# preamp_transistor.net
KiCad netlist of a schematic drawn in EasyEDA
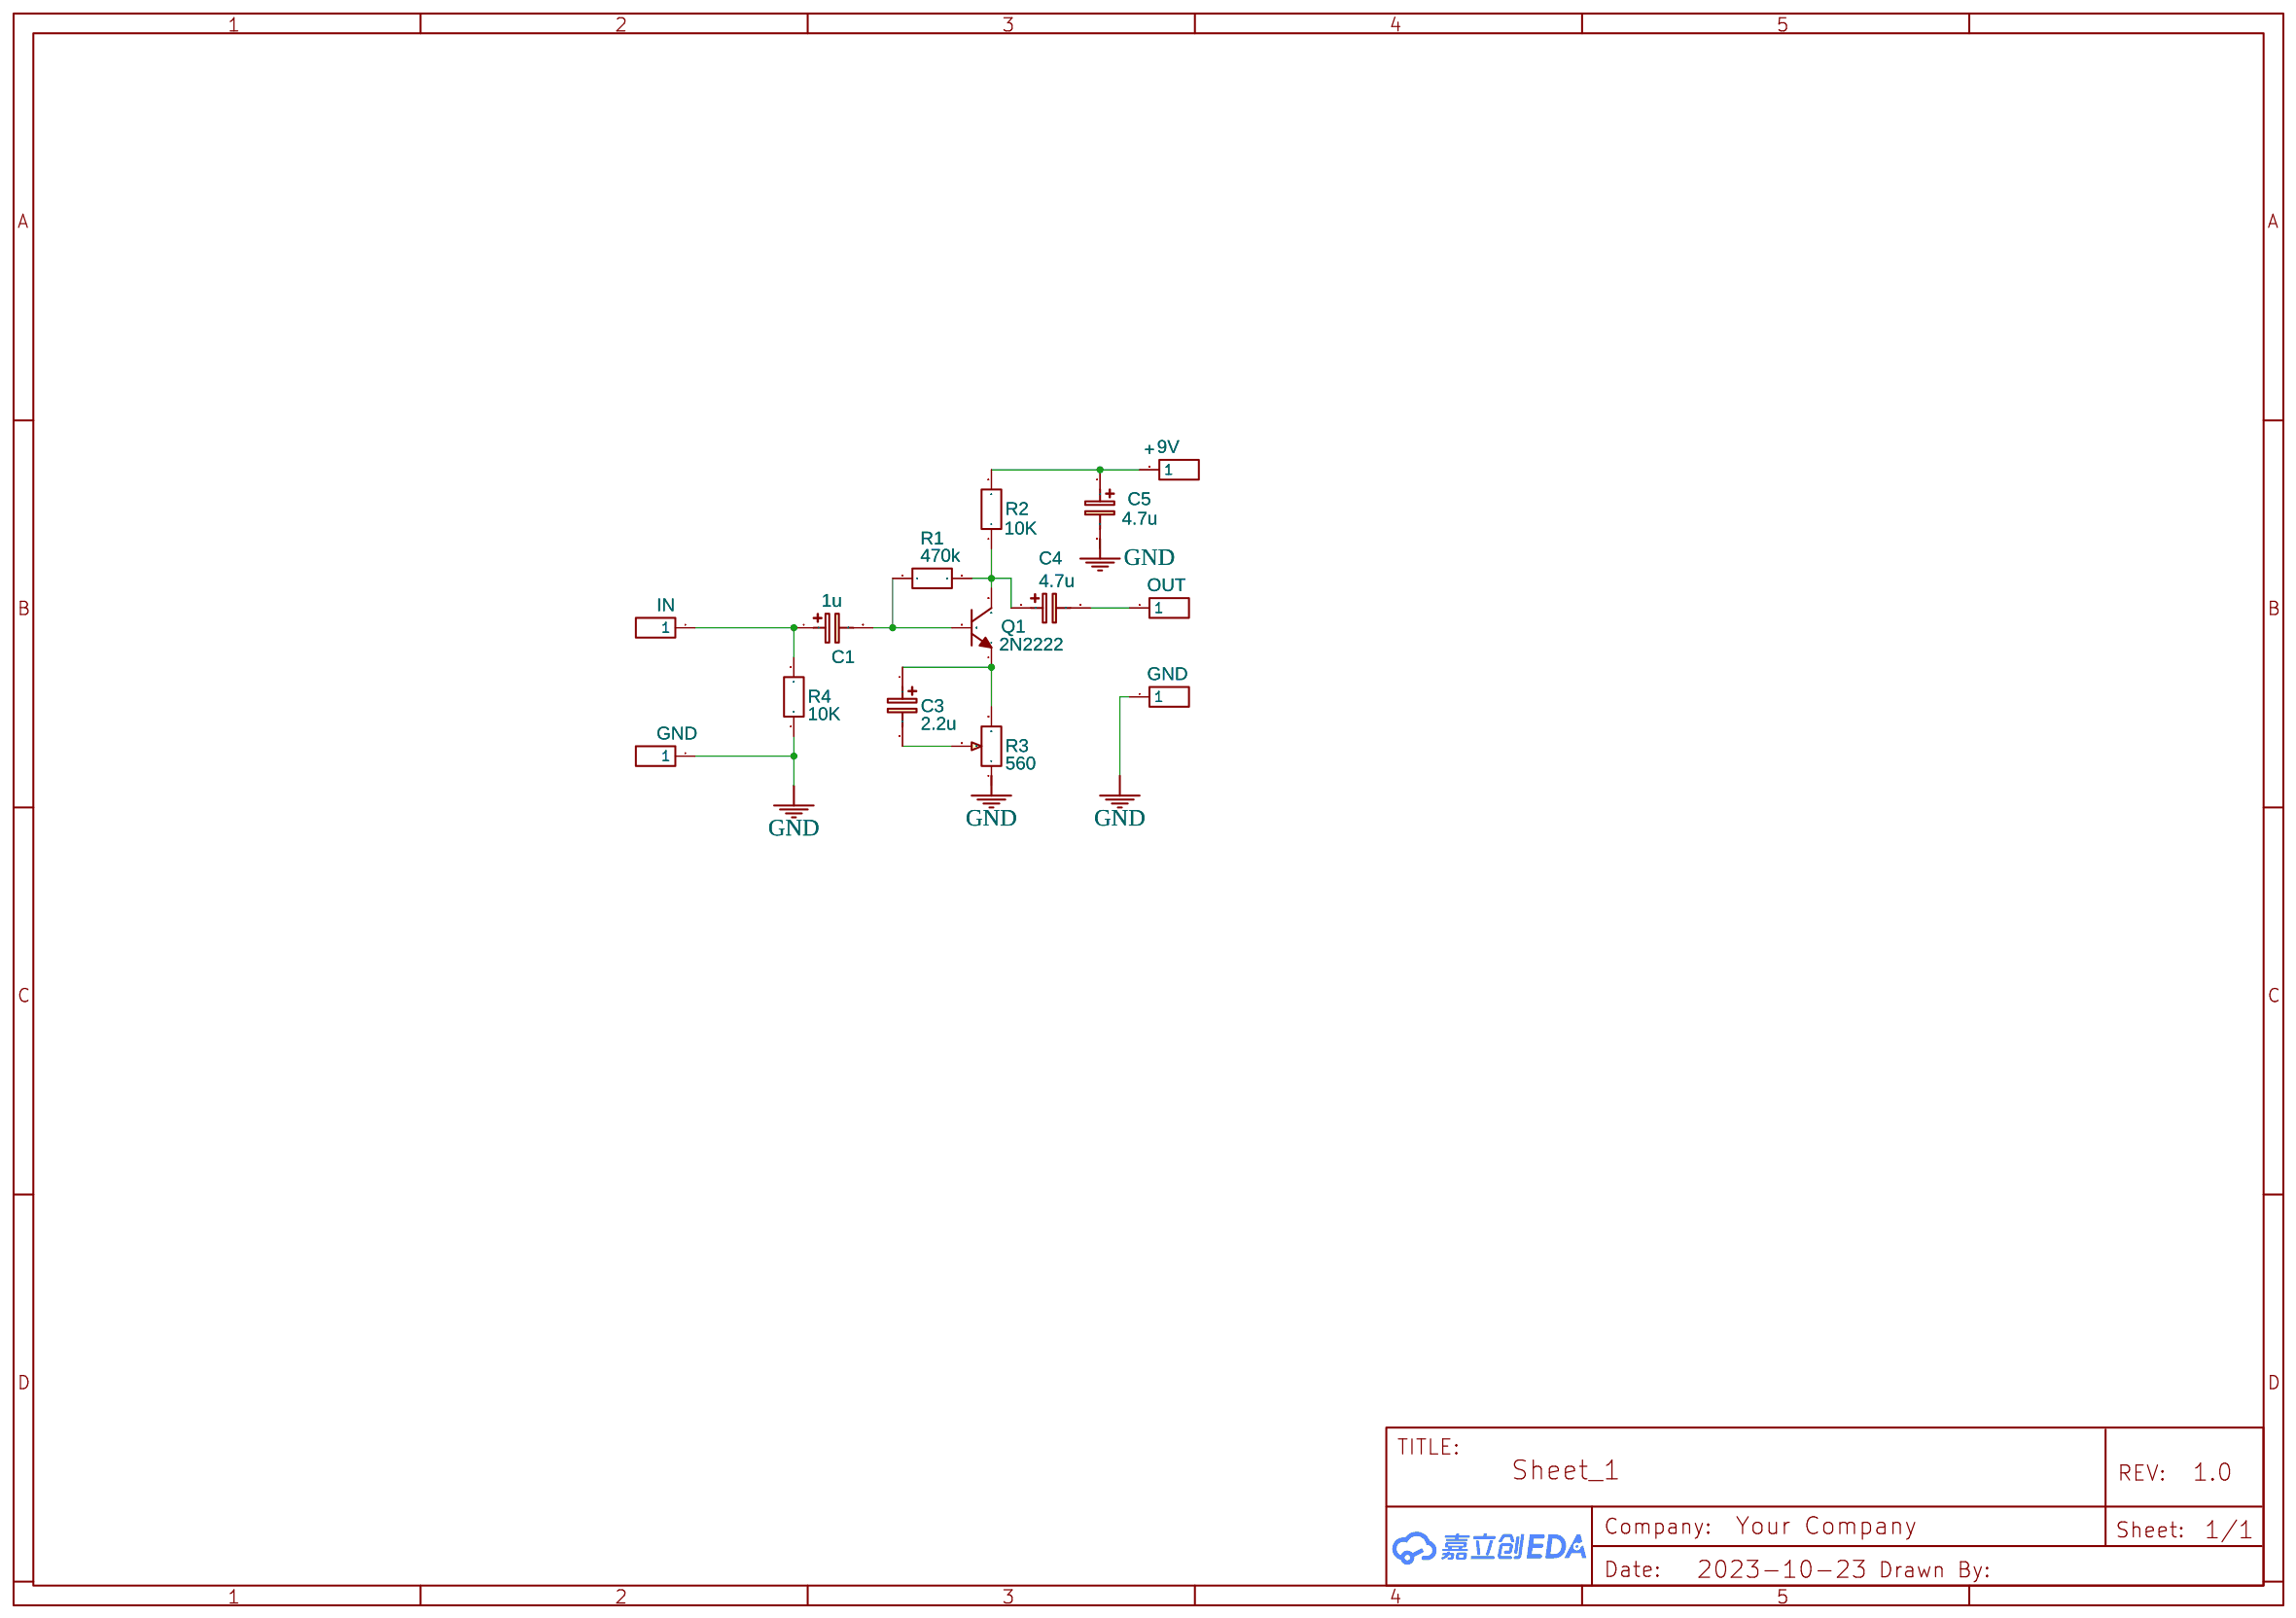
[diagram p0: schematic sheet]

(export (version "E")
  (design (tool "Eeschema 10.0.6"))
  (components
    (comp (ref "+")
      (value "9V")
      (fields (field (name "BOM_Supplier Part") "C81276"))
      (libsource (lib "") (part "HDR-M-2.54_1x1_3"))
    )
    (comp (ref "-")
      (value "GND")
      (fields (field (name "BOM_Supplier Part") "C81276"))
      (libsource (lib "") (part "HDR-M-2.54_1x1_4"))
    )
    (comp (ref "C1") (value "1u") (libsource (lib "") (part "C_Tan_SMD_A_EU_2")))
    (comp (ref "C3") (value "2.2u") (libsource (lib "") (part "C_Tan_SMD_A_EU_3")))
    (comp (ref "C4") (value "4.7u") (libsource (lib "") (part "C_Tan_SMD_A_EU")))
    (comp (ref "C5") (value "4.7u") (libsource (lib "") (part "C_Tan_SMD_A_EU_1")))
    (comp (ref "IGND")
      (value "GND")
      (fields (field (name "BOM_Supplier Part") "C81276"))
      (libsource (lib "") (part "HDR-M-2.54_1x1"))
    )
    (comp (ref "IN")
      (value "IN")
      (fields (field (name "BOM_Supplier Part") "C81276"))
      (libsource (lib "") (part "HDR-M-2.54_1x1_1"))
    )
    (comp (ref "OUT")
      (value "OUT")
      (fields (field (name "BOM_Supplier Part") "C81276"))
      (libsource (lib "") (part "HDR-M-2.54_1x1_2"))
    )
    (comp (ref "Q1")
      (value "2N2222")
      (fields
        (field (name "BOM_Manufacturer Part") "2n3904S-RTK/PS")
        (field (name "BOM_Supplier Part") "C18536")
      )
      (libsource (lib "") (part "2N3904(SOT-23)"))
    )
    (comp (ref "R1") (value "470k") (libsource (lib "") (part "R_0603_EU_1")))
    (comp (ref "R2") (value "10K") (libsource (lib "") (part "R_0603_EU")))
    (comp (ref "R3")
      (value "560")
      (fields (field (name "Manufacturer Part") "RM063-103 10K") (field (name "Manufacturer") "JML"))
      (libsource (lib "") (part "RM063-103 10K"))
    )
    (comp (ref "R4") (value "10K") (libsource (lib "") (part "R_0603_EU")))
  )
  (nets
    (net (code "1") (name "GND") (class "Default")
      (node (ref "-") (pin "1") (pinfunction "1_1") (pintype "input"))
      (node (ref "C5") (pin "2") (pinfunction "2_2") (pintype "unspecified"))
      (node (ref "IGND") (pin "1") (pinfunction "1_1") (pintype "input"))
      (node (ref "R3") (pin "1") (pinfunction "1_1") (pintype "input"))
      (node (ref "R4") (pin "1") (pinfunction "1_1") (pintype "unspecified"))
    )
    (net (code "2") (name "Net-(+-Pad1)") (class "Default")
      (node (ref "+") (pin "1") (pinfunction "1_1") (pintype "input"))
      (node (ref "C5") (pin "1") (pinfunction "1_1") (pintype "unspecified"))
      (node (ref "R2") (pin "2") (pinfunction "2_2") (pintype "unspecified"))
    )
    (net (code "3") (name "Net-(C1-Pad1)") (class "Default")
      (node (ref "C1") (pin "1") (pinfunction "1_1") (pintype "unspecified"))
      (node (ref "IN") (pin "1") (pinfunction "1_1") (pintype "input"))
      (node (ref "R4") (pin "2") (pinfunction "2_2") (pintype "unspecified"))
    )
    (net (code "4") (name "Net-(C3-Pad2)") (class "Default")
      (node (ref "C3") (pin "2") (pinfunction "2_2") (pintype "unspecified"))
      (node (ref "R3") (pin "2") (pinfunction "2_2") (pintype "input"))
    )
    (net (code "5") (name "Net-(C4-Pad2)") (class "Default")
      (node (ref "C4") (pin "2") (pinfunction "2_2") (pintype "unspecified"))
      (node (ref "OUT") (pin "1") (pinfunction "1_1") (pintype "input"))
    )
    (net (code "6") (name "Net-(Q1-B)") (class "Default")
      (node (ref "C1") (pin "2") (pinfunction "2_2") (pintype "unspecified"))
      (node (ref "Q1") (pin "2") (pinfunction "B_2") (pintype "input"))
      (node (ref "R1") (pin "1") (pinfunction "1_1") (pintype "unspecified"))
    )
    (net (code "7") (name "Net-(Q1-C)") (class "Default")
      (node (ref "C4") (pin "1") (pinfunction "1_1") (pintype "unspecified"))
      (node (ref "Q1") (pin "3") (pinfunction "C_3") (pintype "input"))
      (node (ref "R1") (pin "2") (pinfunction "2_2") (pintype "unspecified"))
      (node (ref "R2") (pin "1") (pinfunction "1_1") (pintype "unspecified"))
    )
    (net (code "8") (name "Net-(Q1-E)") (class "Default")
      (node (ref "C3") (pin "1") (pinfunction "1_1") (pintype "unspecified"))
      (node (ref "Q1") (pin "1") (pinfunction "E_1") (pintype "input"))
      (node (ref "R3") (pin "3") (pinfunction "3_3") (pintype "input"))
    )
  )
)
